# SubBus12.net
KiCad netlist of a schematic drawn in Altium Designer
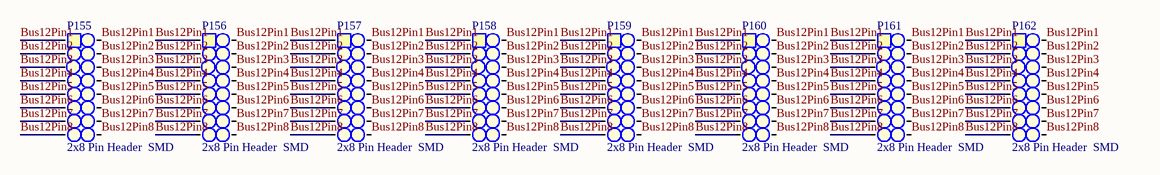
[diagram p0: SubBus12.SchDoc]

(export (version "E")
  (design (tool "Eeschema 10.0.6"))
  (components
    (comp (ref "P155")
      (value "2x8 Pin Header  SMD")
      (footprint "2X8_SMD_PH_2.54")
      (description "2.54mm, SMD")
      (libsource (lib "jclib") (part "2x8 Pin Header  SMD"))
    )
    (comp (ref "P156")
      (value "2x8 Pin Header  SMD")
      (footprint "2X8_SMD_PH_2.54")
      (description "2.54mm, SMD")
      (libsource (lib "jclib") (part "2x8 Pin Header  SMD"))
    )
    (comp (ref "P157")
      (value "2x8 Pin Header  SMD")
      (footprint "2X8_SMD_PH_2.54")
      (description "2.54mm, SMD")
      (libsource (lib "jclib") (part "2x8 Pin Header  SMD"))
    )
    (comp (ref "P158")
      (value "2x8 Pin Header  SMD")
      (footprint "2X8_SMD_PH_2.54")
      (description "2.54mm, SMD")
      (libsource (lib "jclib") (part "2x8 Pin Header  SMD"))
    )
    (comp (ref "P159")
      (value "2x8 Pin Header  SMD")
      (footprint "2X8_SMD_PH_2.54")
      (description "2.54mm, SMD")
      (libsource (lib "jclib") (part "2x8 Pin Header  SMD"))
    )
    (comp (ref "P160")
      (value "2x8 Pin Header  SMD")
      (footprint "2X8_SMD_PH_2.54")
      (description "2.54mm, SMD")
      (libsource (lib "jclib") (part "2x8 Pin Header  SMD"))
    )
    (comp (ref "P161")
      (value "2x8 Pin Header  SMD")
      (footprint "2X8_SMD_PH_2.54")
      (description "2.54mm, SMD")
      (libsource (lib "jclib") (part "2x8 Pin Header  SMD"))
    )
    (comp (ref "P162")
      (value "2x8 Pin Header  SMD")
      (footprint "2X8_SMD_PH_2.54")
      (description "2.54mm, SMD")
      (libsource (lib "jclib") (part "2x8 Pin Header  SMD"))
    )
  )
  (nets
    (net (code "1") (name "/Bus12Pin1") (class "Default")
      (node (ref "P155") (pin "1") (pinfunction "1_1") (pintype "passive"))
      (node (ref "P155") (pin "16") (pinfunction "16_16") (pintype "passive"))
      (node (ref "P156") (pin "1") (pinfunction "1_1") (pintype "passive"))
      (node (ref "P156") (pin "16") (pinfunction "16_16") (pintype "passive"))
      (node (ref "P157") (pin "1") (pinfunction "1_1") (pintype "passive"))
      (node (ref "P157") (pin "16") (pinfunction "16_16") (pintype "passive"))
      (node (ref "P158") (pin "1") (pinfunction "1_1") (pintype "passive"))
      (node (ref "P158") (pin "16") (pinfunction "16_16") (pintype "passive"))
      (node (ref "P159") (pin "1") (pinfunction "1_1") (pintype "passive"))
      (node (ref "P159") (pin "16") (pinfunction "16_16") (pintype "passive"))
      (node (ref "P160") (pin "1") (pinfunction "1_1") (pintype "passive"))
      (node (ref "P160") (pin "16") (pinfunction "16_16") (pintype "passive"))
      (node (ref "P161") (pin "1") (pinfunction "1_1") (pintype "passive"))
      (node (ref "P161") (pin "16") (pinfunction "16_16") (pintype "passive"))
      (node (ref "P162") (pin "1") (pinfunction "1_1") (pintype "passive"))
      (node (ref "P162") (pin "16") (pinfunction "16_16") (pintype "passive"))
    )
    (net (code "2") (name "/Bus12Pin2") (class "Default")
      (node (ref "P155") (pin "15") (pinfunction "15_15") (pintype "passive"))
      (node (ref "P155") (pin "2") (pinfunction "2_2") (pintype "passive"))
      (node (ref "P156") (pin "15") (pinfunction "15_15") (pintype "passive"))
      (node (ref "P156") (pin "2") (pinfunction "2_2") (pintype "passive"))
      (node (ref "P157") (pin "15") (pinfunction "15_15") (pintype "passive"))
      (node (ref "P157") (pin "2") (pinfunction "2_2") (pintype "passive"))
      (node (ref "P158") (pin "15") (pinfunction "15_15") (pintype "passive"))
      (node (ref "P158") (pin "2") (pinfunction "2_2") (pintype "passive"))
      (node (ref "P159") (pin "15") (pinfunction "15_15") (pintype "passive"))
      (node (ref "P159") (pin "2") (pinfunction "2_2") (pintype "passive"))
      (node (ref "P160") (pin "15") (pinfunction "15_15") (pintype "passive"))
      (node (ref "P160") (pin "2") (pinfunction "2_2") (pintype "passive"))
      (node (ref "P161") (pin "15") (pinfunction "15_15") (pintype "passive"))
      (node (ref "P161") (pin "2") (pinfunction "2_2") (pintype "passive"))
      (node (ref "P162") (pin "15") (pinfunction "15_15") (pintype "passive"))
      (node (ref "P162") (pin "2") (pinfunction "2_2") (pintype "passive"))
    )
    (net (code "3") (name "/Bus12Pin3") (class "Default")
      (node (ref "P155") (pin "14") (pinfunction "14_14") (pintype "passive"))
      (node (ref "P155") (pin "3") (pinfunction "3_3") (pintype "passive"))
      (node (ref "P156") (pin "14") (pinfunction "14_14") (pintype "passive"))
      (node (ref "P156") (pin "3") (pinfunction "3_3") (pintype "passive"))
      (node (ref "P157") (pin "14") (pinfunction "14_14") (pintype "passive"))
      (node (ref "P157") (pin "3") (pinfunction "3_3") (pintype "passive"))
      (node (ref "P158") (pin "14") (pinfunction "14_14") (pintype "passive"))
      (node (ref "P158") (pin "3") (pinfunction "3_3") (pintype "passive"))
      (node (ref "P159") (pin "14") (pinfunction "14_14") (pintype "passive"))
      (node (ref "P159") (pin "3") (pinfunction "3_3") (pintype "passive"))
      (node (ref "P160") (pin "14") (pinfunction "14_14") (pintype "passive"))
      (node (ref "P160") (pin "3") (pinfunction "3_3") (pintype "passive"))
      (node (ref "P161") (pin "14") (pinfunction "14_14") (pintype "passive"))
      (node (ref "P161") (pin "3") (pinfunction "3_3") (pintype "passive"))
      (node (ref "P162") (pin "14") (pinfunction "14_14") (pintype "passive"))
      (node (ref "P162") (pin "3") (pinfunction "3_3") (pintype "passive"))
    )
    (net (code "4") (name "/Bus12Pin4") (class "Default")
      (node (ref "P155") (pin "13") (pinfunction "13_13") (pintype "passive"))
      (node (ref "P155") (pin "4") (pinfunction "4_4") (pintype "passive"))
      (node (ref "P156") (pin "13") (pinfunction "13_13") (pintype "passive"))
      (node (ref "P156") (pin "4") (pinfunction "4_4") (pintype "passive"))
      (node (ref "P157") (pin "13") (pinfunction "13_13") (pintype "passive"))
      (node (ref "P157") (pin "4") (pinfunction "4_4") (pintype "passive"))
      (node (ref "P158") (pin "13") (pinfunction "13_13") (pintype "passive"))
      (node (ref "P158") (pin "4") (pinfunction "4_4") (pintype "passive"))
      (node (ref "P159") (pin "13") (pinfunction "13_13") (pintype "passive"))
      (node (ref "P159") (pin "4") (pinfunction "4_4") (pintype "passive"))
      (node (ref "P160") (pin "13") (pinfunction "13_13") (pintype "passive"))
      (node (ref "P160") (pin "4") (pinfunction "4_4") (pintype "passive"))
      (node (ref "P161") (pin "13") (pinfunction "13_13") (pintype "passive"))
      (node (ref "P161") (pin "4") (pinfunction "4_4") (pintype "passive"))
      (node (ref "P162") (pin "13") (pinfunction "13_13") (pintype "passive"))
      (node (ref "P162") (pin "4") (pinfunction "4_4") (pintype "passive"))
    )
    (net (code "5") (name "/Bus12Pin5") (class "Default")
      (node (ref "P155") (pin "12") (pinfunction "12_12") (pintype "passive"))
      (node (ref "P155") (pin "5") (pinfunction "5_5") (pintype "passive"))
      (node (ref "P156") (pin "12") (pinfunction "12_12") (pintype "passive"))
      (node (ref "P156") (pin "5") (pinfunction "5_5") (pintype "passive"))
      (node (ref "P157") (pin "12") (pinfunction "12_12") (pintype "passive"))
      (node (ref "P157") (pin "5") (pinfunction "5_5") (pintype "passive"))
      (node (ref "P158") (pin "12") (pinfunction "12_12") (pintype "passive"))
      (node (ref "P158") (pin "5") (pinfunction "5_5") (pintype "passive"))
      (node (ref "P159") (pin "12") (pinfunction "12_12") (pintype "passive"))
      (node (ref "P159") (pin "5") (pinfunction "5_5") (pintype "passive"))
      (node (ref "P160") (pin "12") (pinfunction "12_12") (pintype "passive"))
      (node (ref "P160") (pin "5") (pinfunction "5_5") (pintype "passive"))
      (node (ref "P161") (pin "12") (pinfunction "12_12") (pintype "passive"))
      (node (ref "P161") (pin "5") (pinfunction "5_5") (pintype "passive"))
      (node (ref "P162") (pin "12") (pinfunction "12_12") (pintype "passive"))
      (node (ref "P162") (pin "5") (pinfunction "5_5") (pintype "passive"))
    )
    (net (code "6") (name "/Bus12Pin6") (class "Default")
      (node (ref "P155") (pin "11") (pinfunction "11_11") (pintype "passive"))
      (node (ref "P155") (pin "6") (pinfunction "6_6") (pintype "passive"))
      (node (ref "P156") (pin "11") (pinfunction "11_11") (pintype "passive"))
      (node (ref "P156") (pin "6") (pinfunction "6_6") (pintype "passive"))
      (node (ref "P157") (pin "11") (pinfunction "11_11") (pintype "passive"))
      (node (ref "P157") (pin "6") (pinfunction "6_6") (pintype "passive"))
      (node (ref "P158") (pin "11") (pinfunction "11_11") (pintype "passive"))
      (node (ref "P158") (pin "6") (pinfunction "6_6") (pintype "passive"))
      (node (ref "P159") (pin "11") (pinfunction "11_11") (pintype "passive"))
      (node (ref "P159") (pin "6") (pinfunction "6_6") (pintype "passive"))
      (node (ref "P160") (pin "11") (pinfunction "11_11") (pintype "passive"))
      (node (ref "P160") (pin "6") (pinfunction "6_6") (pintype "passive"))
      (node (ref "P161") (pin "11") (pinfunction "11_11") (pintype "passive"))
      (node (ref "P161") (pin "6") (pinfunction "6_6") (pintype "passive"))
      (node (ref "P162") (pin "11") (pinfunction "11_11") (pintype "passive"))
      (node (ref "P162") (pin "6") (pinfunction "6_6") (pintype "passive"))
    )
    (net (code "7") (name "/Bus12Pin7") (class "Default")
      (node (ref "P155") (pin "10") (pinfunction "10_10") (pintype "passive"))
      (node (ref "P155") (pin "7") (pinfunction "7_7") (pintype "passive"))
      (node (ref "P156") (pin "10") (pinfunction "10_10") (pintype "passive"))
      (node (ref "P156") (pin "7") (pinfunction "7_7") (pintype "passive"))
      (node (ref "P157") (pin "10") (pinfunction "10_10") (pintype "passive"))
      (node (ref "P157") (pin "7") (pinfunction "7_7") (pintype "passive"))
      (node (ref "P158") (pin "10") (pinfunction "10_10") (pintype "passive"))
      (node (ref "P158") (pin "7") (pinfunction "7_7") (pintype "passive"))
      (node (ref "P159") (pin "10") (pinfunction "10_10") (pintype "passive"))
      (node (ref "P159") (pin "7") (pinfunction "7_7") (pintype "passive"))
      (node (ref "P160") (pin "10") (pinfunction "10_10") (pintype "passive"))
      (node (ref "P160") (pin "7") (pinfunction "7_7") (pintype "passive"))
      (node (ref "P161") (pin "10") (pinfunction "10_10") (pintype "passive"))
      (node (ref "P161") (pin "7") (pinfunction "7_7") (pintype "passive"))
      (node (ref "P162") (pin "10") (pinfunction "10_10") (pintype "passive"))
      (node (ref "P162") (pin "7") (pinfunction "7_7") (pintype "passive"))
    )
    (net (code "8") (name "/Bus12Pin8") (class "Default")
      (node (ref "P155") (pin "8") (pinfunction "8_8") (pintype "passive"))
      (node (ref "P155") (pin "9") (pinfunction "9_9") (pintype "passive"))
      (node (ref "P156") (pin "8") (pinfunction "8_8") (pintype "passive"))
      (node (ref "P156") (pin "9") (pinfunction "9_9") (pintype "passive"))
      (node (ref "P157") (pin "8") (pinfunction "8_8") (pintype "passive"))
      (node (ref "P157") (pin "9") (pinfunction "9_9") (pintype "passive"))
      (node (ref "P158") (pin "8") (pinfunction "8_8") (pintype "passive"))
      (node (ref "P158") (pin "9") (pinfunction "9_9") (pintype "passive"))
      (node (ref "P159") (pin "8") (pinfunction "8_8") (pintype "passive"))
      (node (ref "P159") (pin "9") (pinfunction "9_9") (pintype "passive"))
      (node (ref "P160") (pin "8") (pinfunction "8_8") (pintype "passive"))
      (node (ref "P160") (pin "9") (pinfunction "9_9") (pintype "passive"))
      (node (ref "P161") (pin "8") (pinfunction "8_8") (pintype "passive"))
      (node (ref "P161") (pin "9") (pinfunction "9_9") (pintype "passive"))
      (node (ref "P162") (pin "8") (pinfunction "8_8") (pintype "passive"))
      (node (ref "P162") (pin "9") (pinfunction "9_9") (pintype "passive"))
    )
  )
)
